# joint_board_motor_drivers.net
KiCad netlist of a schematic drawn in Altium Designer
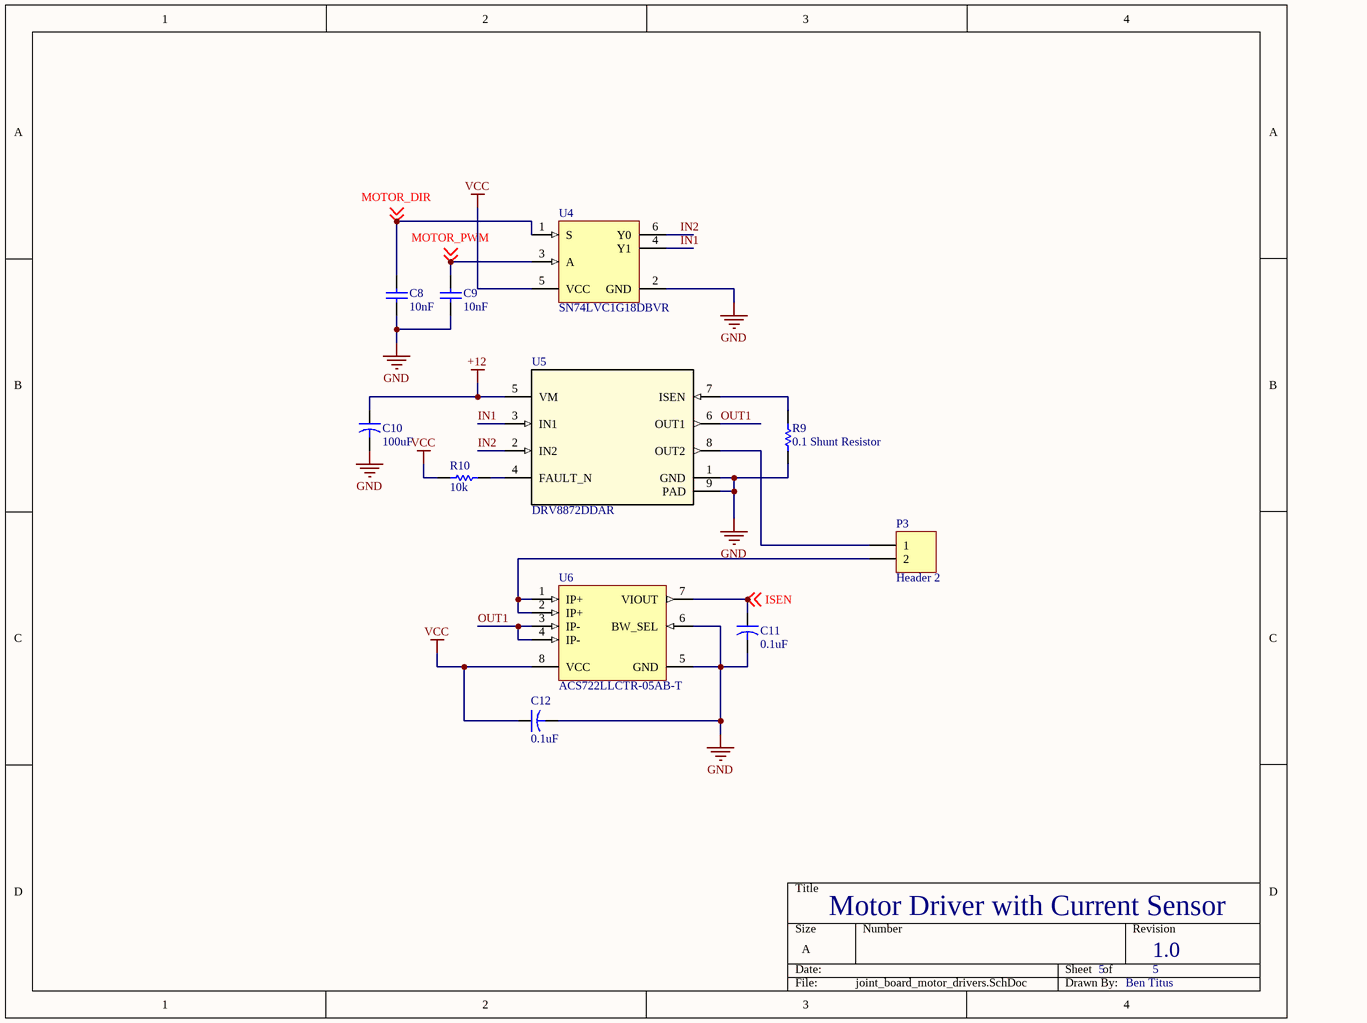
[diagram p0: joint_board_motor_drivers.SchDoc]

(export (version "E")
  (design (tool "Eeschema 10.0.6"))
  (components
    (comp (ref "C8")
      (value "10nF")
      (footprint "CAPC0805(2012)145_L")
      (description "0805 (2012 Metric) Chip Capacitor")
      (libsource (lib "Altium Content Vault") (part "CAP_5"))
    )
    (comp (ref "C9")
      (value "10nF")
      (footprint "CAPC0805(2012)145_L")
      (description "0805 (2012 Metric) Chip Capacitor")
      (libsource (lib "Altium Content Vault") (part "CAP_5"))
    )
    (comp (ref "C10")
      (value "100uF")
      (footprint "CAPR5-4X5")
      (description "100uF Filter Capacitor")
      (fields (field (name "PUBLISHER") "Altium Limited"))
      (libsource (lib "Miscellaneous Devices") (part "Cap2"))
    )
    (comp (ref "C11")
      (value "0.1uF")
      (footprint "CAPR5-4X5")
      (description "Capacitor")
      (fields (field (name "PUBLISHER") "Altium Limited"))
      (libsource (lib "Miscellaneous Devices") (part "Cap2"))
    )
    (comp (ref "C12")
      (value "0.1uF")
      (footprint "CAPR5-4X5")
      (description "Capacitor")
      (fields (field (name "PUBLISHER") "Altium Limited"))
      (libsource (lib "Miscellaneous Devices") (part "Cap2"))
    )
    (comp (ref "P3")
      (value "Header 2")
      (footprint "HDR1X2")
      (description "Header, 2-Pin")
      (fields (field (name "PUBLISHER") "Altium Limited"))
      (libsource (lib "Miscellaneous Connectors") (part "Header 2"))
    )
    (comp (ref "R9")
      (value "0.1 Shunt Resistor")
      (footprint "RESC2512(6432)_L")
      (description "2512 (6432 Metric) Chip Resistor")
      (libsource (lib "Altium Content Vault") (part "RES_3"))
    )
    (comp (ref "R10")
      (value "10k")
      (footprint "RESC0805(2012)_L")
      (description "0805 (2012 Metric) Chip Resistor")
      (libsource (lib "Altium Content Vault") (part "RES_3"))
    )
    (comp (ref "U4")
      (value "SN74LVC1G18DBVR")
      (footprint "DBV0006A_L")
      (description "One of Two Noninverting Demultiplexer with 3-State Deselected Output, DBV0006A, LARGE T&R")
      (fields
        (field (name "MANUFACTURER") "Texas Instruments")
        (field (name "GENERIC PART NUMBER") "SN74LVC1G18")
      )
      (libsource (lib "Altium Content Vault") (part "TI-SN74LVC1G18-6"))
    )
    (comp (ref "U5")
      (value "DRV8872DDAR")
      (footprint "DDA0008H_N")
      (description "Imported")
      (fields
        (field (name "ALTERNATE_PARTNUMBER") "DRV8872DDA")
        (field (name "MANUFACTURER") "Texas Instruments")
      )
      (libsource (lib "Custom_Lib") (part "DRV8872DDAR"))
    )
    (comp (ref "U6")
      (value "ACS722LLCTR-05AB-T")
      (footprint "ALEG-LC-8_V")
      (libsource (lib "Altium Content Vault") (part "ALEG-ACS722-SOIC-8"))
    )
  )
  (nets
    (net (code "1") (name "+12") (class "Default")
      (node (ref "C10") (pin "1") (pinfunction "1_1") (pintype "passive"))
      (node (ref "U5") (pin "5") (pinfunction "VM_5") (pintype "power_in"))
    )
    (net (code "2") (name "/IN1") (class "Default")
      (node (ref "U4") (pin "4") (pinfunction "Y1_4") (pintype "tri_state"))
      (node (ref "U5") (pin "3") (pinfunction "IN1_3") (pintype "input"))
    )
    (net (code "3") (name "/IN2") (class "Default")
      (node (ref "U4") (pin "6") (pinfunction "Y0_6") (pintype "tri_state"))
      (node (ref "U5") (pin "2") (pinfunction "IN2_2") (pintype "input"))
    )
    (net (code "4") (name "/OUT1") (class "Default")
      (node (ref "U5") (pin "6") (pinfunction "OUT1_6") (pintype "output"))
      (node (ref "U6") (pin "3") (pinfunction "IP-_3") (pintype "input"))
      (node (ref "U6") (pin "4") (pinfunction "IP-_4") (pintype "input"))
    )
    (net (code "5") (name "GND") (class "Default")
      (node (ref "C10") (pin "2") (pinfunction "2_2") (pintype "passive"))
      (node (ref "C11") (pin "2") (pinfunction "2_2") (pintype "passive"))
      (node (ref "C12") (pin "2") (pinfunction "2_2") (pintype "passive"))
      (node (ref "C8") (pin "1") (pinfunction "1_1") (pintype "passive"))
      (node (ref "C9") (pin "1") (pinfunction "1_1") (pintype "passive"))
      (node (ref "R9") (pin "1") (pinfunction "1_1") (pintype "passive"))
      (node (ref "U4") (pin "2") (pinfunction "GND_2") (pintype "power_in"))
      (node (ref "U5") (pin "1") (pinfunction "GND_1") (pintype "power_in"))
      (node (ref "U5") (pin "9") (pinfunction "PAD_9") (pintype "power_in"))
      (node (ref "U6") (pin "5") (pinfunction "GND_5") (pintype "power_in"))
      (node (ref "U6") (pin "6") (pinfunction "BW_SEL_6") (pintype "input"))
    )
    (net (code "6") (name "ISEN") (class "Default")
      (node (ref "C11") (pin "1") (pinfunction "1_1") (pintype "passive"))
      (node (ref "U6") (pin "7") (pinfunction "VIOUT_7") (pintype "output"))
    )
    (net (code "7") (name "MOTOR_DIR") (class "Default")
      (node (ref "C8") (pin "2") (pinfunction "2_2") (pintype "passive"))
      (node (ref "U4") (pin "1") (pinfunction "S_1") (pintype "input"))
    )
    (net (code "8") (name "MOTOR_PWM") (class "Default")
      (node (ref "C9") (pin "2") (pinfunction "2_2") (pintype "passive"))
      (node (ref "U4") (pin "3") (pinfunction "A_3") (pintype "input"))
    )
    (net (code "9") (name "Net-(P3-Pad2)") (class "Default")
      (node (ref "P3") (pin "2") (pinfunction "2_2") (pintype "passive"))
      (node (ref "U6") (pin "1") (pinfunction "IP+_1") (pintype "input"))
      (node (ref "U6") (pin "2") (pinfunction "IP+_2") (pintype "input"))
    )
    (net (code "10") (name "Net-(U5-FAULT_N)") (class "Default")
      (node (ref "R10") (pin "2") (pinfunction "2_2") (pintype "passive"))
      (node (ref "U5") (pin "4") (pinfunction "FAULT_N_4") (pintype "open_collector"))
    )
    (net (code "11") (name "Net-(U5-ISEN)") (class "Default")
      (node (ref "R9") (pin "2") (pinfunction "2_2") (pintype "passive"))
      (node (ref "U5") (pin "7") (pinfunction "ISEN_7") (pintype "input"))
    )
    (net (code "12") (name "Net-(U5-OUT2)") (class "Default")
      (node (ref "P3") (pin "1") (pinfunction "1_1") (pintype "passive"))
      (node (ref "U5") (pin "8") (pinfunction "OUT2_8") (pintype "output"))
    )
    (net (code "13") (name "VCC") (class "Default")
      (node (ref "C12") (pin "1") (pinfunction "1_1") (pintype "passive"))
      (node (ref "R10") (pin "1") (pinfunction "1_1") (pintype "passive"))
      (node (ref "U4") (pin "5") (pinfunction "VCC_5") (pintype "power_in"))
      (node (ref "U6") (pin "8") (pinfunction "VCC_8") (pintype "power_in"))
    )
  )
)
